# STM32F103T8.net
KiCad netlist of a schematic drawn in Altium Designer
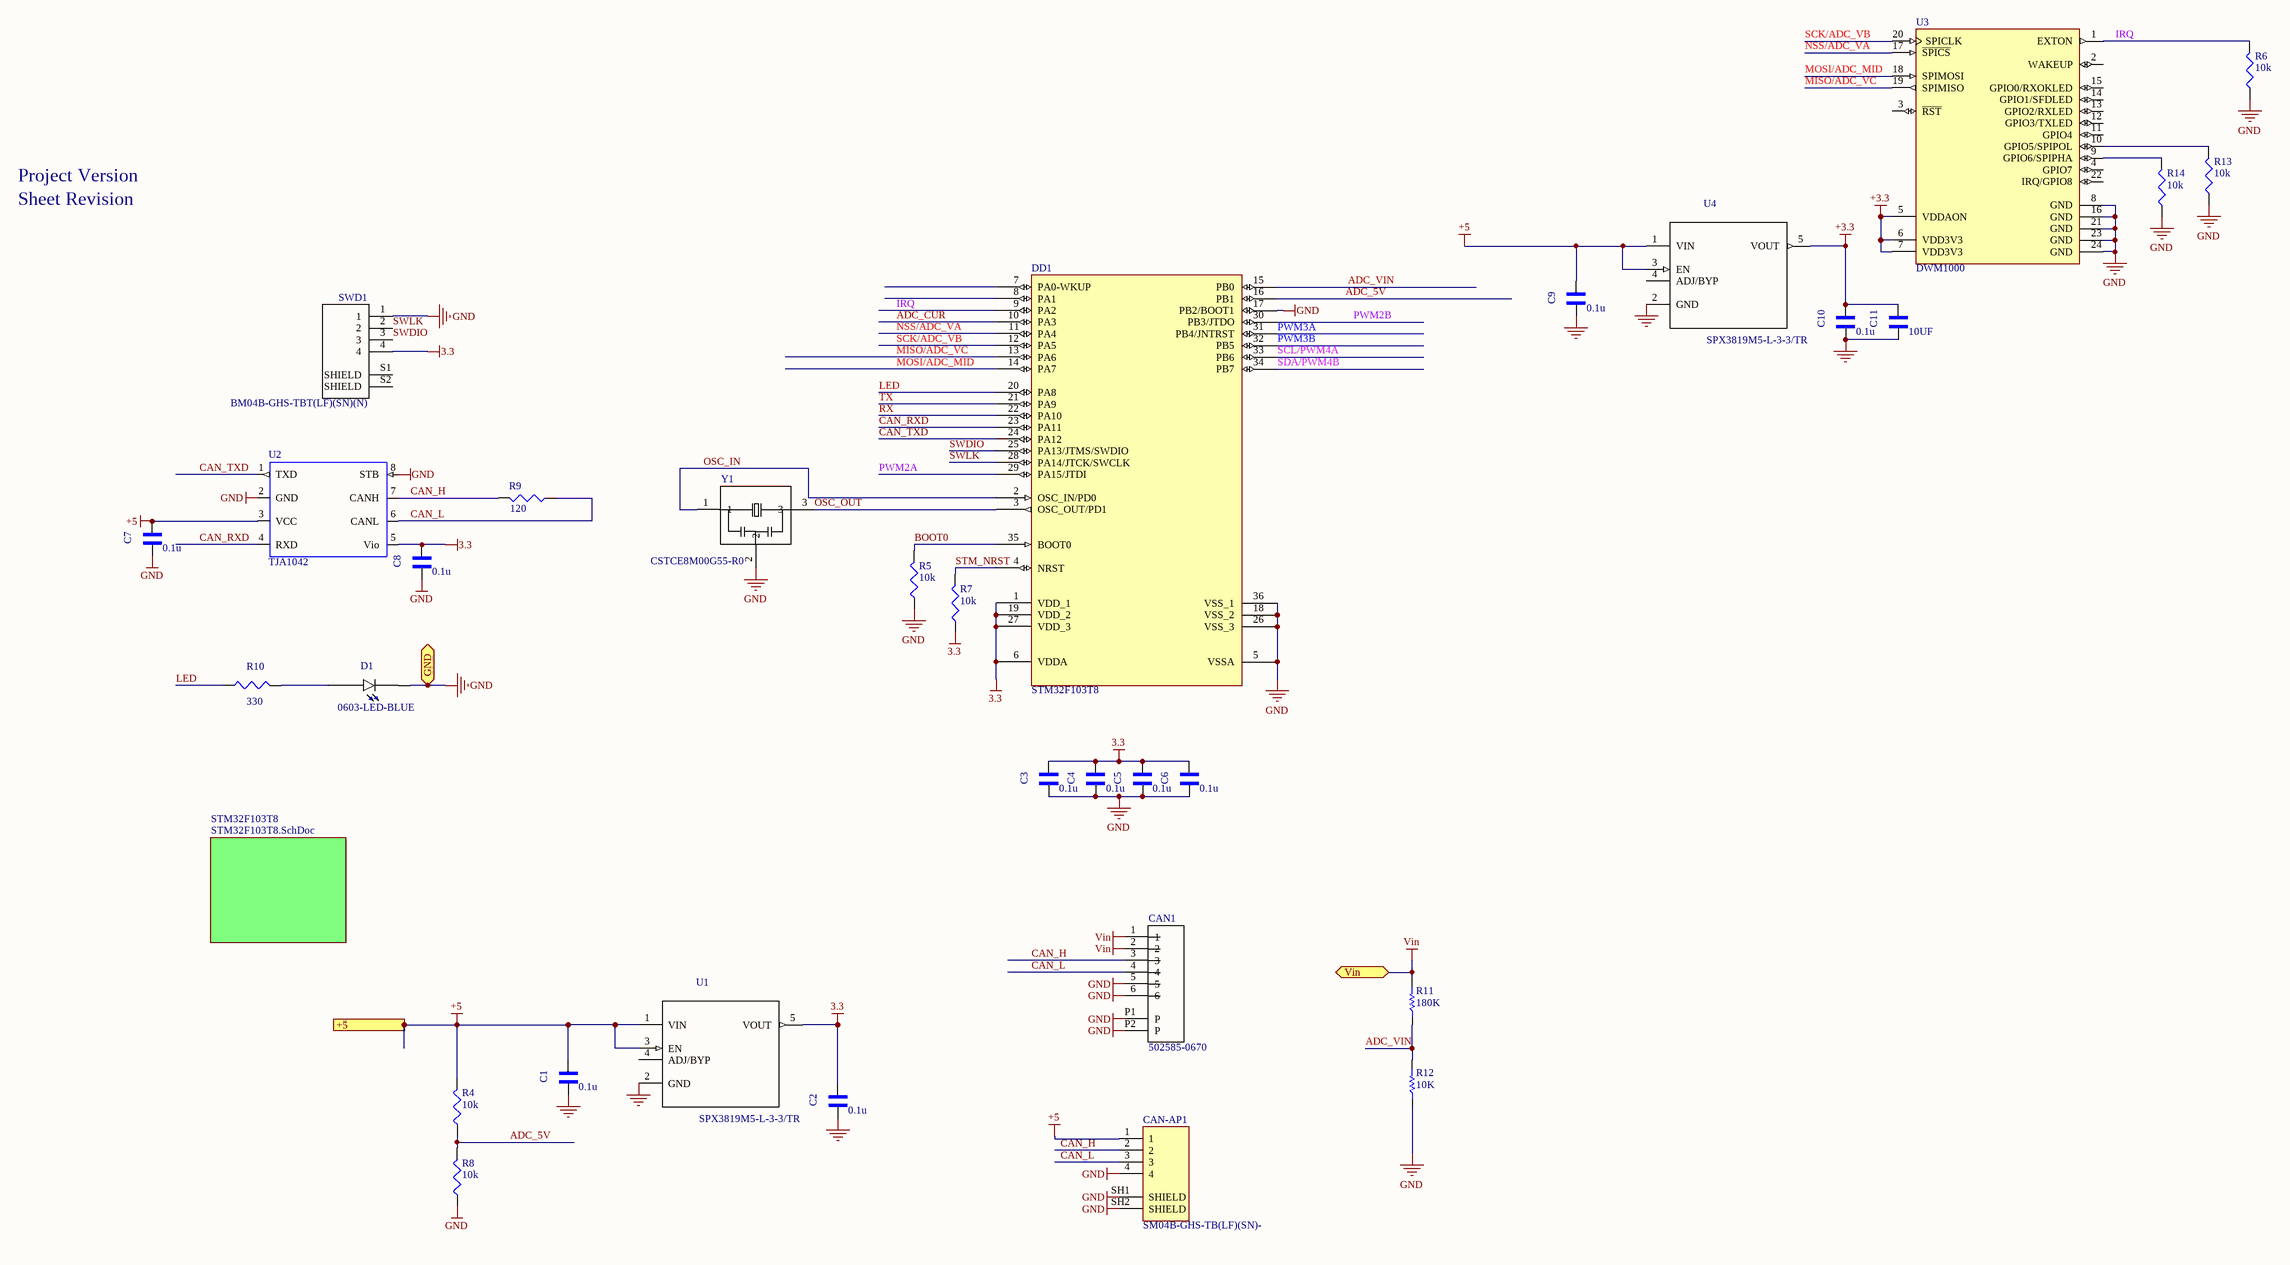
[diagram p0: STM32F103T8.SchDoc]

(export (version "E")
  (design (tool "Eeschema 10.0.6"))
  (components
    (comp (ref "C1")
      (value "0.1u")
      (footprint "*CAPC1608X90")
      (description "Cap Thin Film 0.1uf 50v 0603")
      (fields (field (name "MF") "AVX") (field (name "MP") "GX035C104MAT2-500"))
      (libsource (lib "lib") (part "GX035C104MAT2-500"))
    )
    (comp (ref "C2")
      (value "0.1u")
      (footprint "*CAPC1608X90")
      (description "Cap Thin Film 0.1uf 50v 0603")
      (fields (field (name "MF") "AVX") (field (name "MP") "GX035C104MAT2-500"))
      (libsource (lib "lib") (part "GX035C104MAT2-500"))
    )
    (comp (ref "C3")
      (value "0.1u")
      (footprint "*CAPC1608X90")
      (description "Cap Thin Film 0.1uf 50v 0603")
      (fields (field (name "MF") "AVX") (field (name "MP") "GX035C104MAT2-500 or CL10B104JB8NNNC"))
      (libsource (lib "lib") (part "GX035C104MAT2-500"))
    )
    (comp (ref "C4")
      (value "0.1u")
      (footprint "*CAPC1608X90")
      (description "Cap Thin Film 0.1uf 50v 0603")
      (fields (field (name "MF") "AVX") (field (name "MP") "GX035C104MAT2-500 or CL10B104JB8NNNC"))
      (libsource (lib "lib") (part "GX035C104MAT2-500"))
    )
    (comp (ref "C5")
      (value "0.1u")
      (footprint "*CAPC1608X90")
      (description "Cap Thin Film 0.1uf 50v 0603")
      (fields (field (name "MF") "AVX") (field (name "MP") "GX035C104MAT2-500 or CL10B104JB8NNNC"))
      (libsource (lib "lib") (part "GX035C104MAT2-500"))
    )
    (comp (ref "C6")
      (value "0.1u")
      (footprint "*CAPC1608X90")
      (description "Cap Thin Film 0.1uf 50v 0603")
      (fields (field (name "MF") "AVX") (field (name "MP") "GX035C104MAT2-500 or CL10B104JB8NNNC"))
      (libsource (lib "lib") (part "GX035C104MAT2-500"))
    )
    (comp (ref "C7")
      (value "0.1u")
      (footprint "*CAPC1608X90")
      (description "Cap Thin Film 0.1uf 50v 0603")
      (fields (field (name "MF") "AVX") (field (name "MP") "GX035C104MAT2-500 or CL10B104JB8NNNC"))
      (libsource (lib "lib") (part "GX035C104MAT2-500"))
    )
    (comp (ref "C8")
      (value "0.1u")
      (footprint "*CAPC1608X90")
      (description "Cap Thin Film 0.1uf 50v 0603")
      (fields (field (name "MF") "AVX") (field (name "MP") "GX035C104MAT2-500 or CL10B104JB8NNNC"))
      (libsource (lib "lib") (part "GX035C104MAT2-500"))
    )
    (comp (ref "C9")
      (value "0.1u")
      (footprint "*CAPC1608X90")
      (description "Cap Thin Film 0.1uf 50v 0603")
      (fields (field (name "MF") "AVX") (field (name "MP") "GX035C104MAT2-500"))
      (libsource (lib "lib") (part "GX035C104MAT2-500"))
    )
    (comp (ref "C10")
      (value "0.1u")
      (footprint "*CAPC1608X90")
      (description "Cap Thin Film 0.1uf 50v 0603")
      (fields (field (name "MF") "AVX") (field (name "MP") "GX035C104MAT2-500"))
      (libsource (lib "lib") (part "GX035C104MAT2-500"))
    )
    (comp (ref "C11")
      (value "10UF")
      (footprint "*CAPC1608X90")
      (description "Cap Thin Film 0.1uf 50v 0603")
      (fields (field (name "MF") "AVX") (field (name "MP") "GX035C104MAT2-500"))
      (libsource (lib "lib") (part "GX035C104MAT2-500"))
    )
    (comp (ref "CAN-AP1")
      (value "SM04B-GHS-TB(LF)(SN)-")
      (footprint "JST_SM04B-GHS-TB(LF)(SN)-")
      (description "Connector Header Surface Mount, Right Angle 4 position 0.049 _1.25mm_")
      (fields (field (name "MP") "SM04B-GHS-TB(LF)(SN)") (field (name "MF") "JST Sales"))
      (libsource (lib "lib") (part "SM04B-GHS-TB(LF)(SN)-"))
    )
    (comp (ref "CAN1")
      (value "502585-0670")
      (footprint "MOLEX_502585-0670")
      (fields (field (name "MF") "Molex"))
      (libsource (lib "lib") (part "502585-0670"))
    )
    (comp (ref "D1")
      (value "0603-LED-BLUE")
      (footprint "*LEDM1608X80_LTE-C1906R-14(Primary)")
      (description "LED IrLED Chip LED 2-Pin SMD T/R")
      (libsource (lib "lib") (part "LTE-C1906R-14"))
    )
    (comp (ref "DD1")
      (value "STM32F103T8")
      (footprint "*QFN50P600X600X100-37N")
      (description "STM32F103T8U6, Микроконтроллер 32BIT ARM 64K FLASH [VFQFPN-36]")
      (fields (field (name "MF") "STM") (field (name "MP") "STM32F103T8U6"))
      (libsource (lib "lib") (part "STM32F103T8"))
    )
    (comp (ref "R4")
      (value "10k")
      (footprint "J1-0603")
      (description "10 kOhms 1 0.1 W 1 10 W Chip Resistor 0603 1608 Metric Thick Film")
      (fields (field (name "MF") "Yageo or NXP") (field (name "MP") "10K 1% 0603"))
      (libsource (lib "CAN_NODE_MINI") (part "RC0603FR-0710KL"))
    )
    (comp (ref "R5")
      (value "10k")
      (footprint "J1-0603")
      (description "10 kOhms 1 0.1 W 1 10 W Chip Resistor 0603 1608 Metric Thick Film")
      (fields (field (name "MF") "Yageo or NXP") (field (name "MP") "10K 1% 0603"))
      (libsource (lib "CAN_NODE_MINI") (part "RC0603FR-0710KL"))
    )
    (comp (ref "R6")
      (value "10k")
      (footprint "J1-0603")
      (description "10 kOhms 1 0.1 W 1 10 W Chip Resistor 0603 1608 Metric Thick Film")
      (fields (field (name "MF") "Yageo or NXP") (field (name "MP") "10K 1% 0603"))
      (libsource (lib "CAN_NODE_MINI") (part "RC0603FR-0710KL"))
    )
    (comp (ref "R7")
      (value "10k")
      (footprint "J1-0603")
      (description "10 kOhms 1 0.1 W 1 10 W Chip Resistor 0603 1608 Metric Thick Film")
      (fields (field (name "MF") "Yageo or NXP") (field (name "MP") "10K 1% 0603"))
      (libsource (lib "CAN_NODE_MINI") (part "RC0603FR-0710KL"))
    )
    (comp (ref "R8")
      (value "10k")
      (footprint "J1-0603")
      (description "10 kOhms 1 0.1 W 1 10 W Chip Resistor 0603 1608 Metric Thick Film")
      (fields (field (name "MF") "Yageo or NXP") (field (name "MP") "10K 1% 0603"))
      (libsource (lib "CAN_NODE_MINI") (part "RC0603FR-0710KL"))
    )
    (comp (ref "R9")
      (value "120")
      (footprint "J1-0603")
      (description "120 Ohms 1 0.1 W 1 10 W Chip Resistor 0603 1608 Metric Thick Film")
      (fields (field (name "MP") "RC0603FR-07120RL") (field (name "Comment") "Res3"))
      (libsource (lib "Miscellaneous Devices") (part "Res3"))
    )
    (comp (ref "R10")
      (value "330")
      (footprint "J1-0603")
      (description "Resistor")
      (fields (field (name "MP") "RC0603FR-07330RL") (field (name "Comment") "Res3"))
      (libsource (lib "Miscellaneous Devices") (part "Res3"))
    )
    (comp (ref "R11")
      (value "180K")
      (footprint "RES 0603 (1608X06L)")
      (description "Resistor")
      (fields (field (name "TOLERANCE") "5%") (field (name "POWER") "1/8 W"))
      (libsource (lib "R2T Team Library") (part "Resistor"))
    )
    (comp (ref "R12")
      (value "10K")
      (footprint "RES 0603 (1608X06L)")
      (description "Resistor")
      (fields (field (name "TOLERANCE") "5%") (field (name "POWER") "1/8 W"))
      (libsource (lib "R2T Team Library") (part "Resistor"))
    )
    (comp (ref "R13")
      (value "10k")
      (footprint "J1-0603")
      (description "10 kOhms 1 0.1 W 1 10 W Chip Resistor 0603 1608 Metric Thick Film")
      (fields (field (name "MF") "Yageo or NXP") (field (name "MP") "10K 1% 0603"))
      (libsource (lib "CAN_NODE_MINI") (part "RC0603FR-0710KL"))
    )
    (comp (ref "R14")
      (value "10k")
      (footprint "J1-0603")
      (description "10 kOhms 1 0.1 W 1 10 W Chip Resistor 0603 1608 Metric Thick Film")
      (fields (field (name "MF") "Yageo or NXP") (field (name "MP") "10K 1% 0603"))
      (libsource (lib "CAN_NODE_MINI") (part "RC0603FR-0710KL"))
    )
    (comp (ref "SWD1")
      (value "BM04B-GHS-TBT(LF)(SN)(N)")
      (footprint "JST_BM04B-GHS-holes")
      (description "Conn Shrouded Header HDR 4 POS 1.25mm Solder ST SMD Reel")
      (fields (field (name "MF") "JST Sales") (field (name "MP") "SM04B-GHS-TB(LF)(SN)"))
      (libsource (lib "lib") (part "BM04B-GHS-TBT(LF)(SN)(N)"))
    )
    (comp (ref "U1")
      (value "SPX3819M5-L-3-3/TR")
      (footprint "*SOT95P280X145-5N")
      (description "Low Dropout Voltage Regulator, Adjustable 0.5A, В±1%, 2.5 to 16 Vin, 5-Pin SOT-23")
      (fields (field (name "MF") "MaxLinear, Inc."))
      (libsource (lib "DC_DC") (part "SPX3819M5-L"))
    )
    (comp (ref "U2")
      (value "TJA1042")
      (footprint "SOT782-1")
      (description "1/1 Transceiver Half CANbus 8-SO")
      (fields (field (name "MF") "NXP USA"))
      (libsource (lib "lib") (part "TJA1042"))
    )
    (comp (ref "U3")
      (value "DWM1000")
      (footprint "DECW-DWM1000-24_V")
      (description "DW M1000 IEEE 802.15.4 -2011 UWB Transceiver Module")
      (fields (field (name "MANUFACTURER") "Decawave"))
      (libsource (lib "Altium Content Vault") (part "DECW-DWM1000-24"))
    )
    (comp (ref "U4")
      (value "SPX3819M5-L-3-3/TR")
      (footprint "*SOT95P280X145-5N")
      (description "Low Dropout Voltage Regulator, Adjustable 0.5A, В±1%, 2.5 to 16 Vin, 5-Pin SOT-23")
      (fields (field (name "MF") "MaxLinear, Inc."))
      (libsource (lib "DC_DC") (part "SPX3819M5-L"))
    )
    (comp (ref "Y1")
      (value "CSTCE8M00G55-R0")
      (footprint "*OSC_CSTCE8M00G55-R0")
      (description "Ceramic Resonator 8MHz ??0.5% _Tol_ ??0.2% _Stability_ 33pF 40Ohm 3-Pin CSMD T/R")
      (fields (field (name "MF") "Murata"))
      (libsource (lib "DC_DC") (part "CSTCE8M00G55-R0"))
    )
  )
  (nets
    (net (code "1") (name "+3.3") (class "Default")
      (node (ref "C10") (pin "1") (pinfunction "1_1") (pintype "passive"))
      (node (ref "C11") (pin "1") (pinfunction "1_1") (pintype "passive"))
      (node (ref "U3") (pin "5") (pinfunction "VDDAON_5") (pintype "power_in"))
      (node (ref "U3") (pin "6") (pinfunction "VDD3V3_6") (pintype "power_in"))
      (node (ref "U3") (pin "7") (pinfunction "VDD3V3_7") (pintype "power_in"))
      (node (ref "U4") (pin "5") (pinfunction "VOUT_5") (pintype "output"))
    )
    (net (code "2") (name "+5") (class "Default")
      (node (ref "C1") (pin "1") (pinfunction "1_1") (pintype "passive"))
      (node (ref "C7") (pin "1") (pinfunction "1_1") (pintype "passive"))
      (node (ref "C9") (pin "1") (pinfunction "1_1") (pintype "passive"))
      (node (ref "CAN-AP1") (pin "1") (pinfunction "1_1") (pintype "passive"))
      (node (ref "R4") (pin "2") (pinfunction "2_2") (pintype "passive"))
      (node (ref "U1") (pin "1") (pinfunction "VIN_1") (pintype "power_in"))
      (node (ref "U1") (pin "3") (pinfunction "EN_3") (pintype "input"))
      (node (ref "U2") (pin "3") (pinfunction "VCC_3") (pintype "power_in"))
      (node (ref "U4") (pin "1") (pinfunction "VIN_1") (pintype "power_in"))
      (node (ref "U4") (pin "3") (pinfunction "EN_3") (pintype "input"))
    )
    (net (code "3") (name "/ADC_5V") (class "Default")
      (node (ref "DD1") (pin "16") (pinfunction "PB1_16") (pintype "bidirectional"))
      (node (ref "R4") (pin "1") (pinfunction "1_1") (pintype "passive"))
      (node (ref "R8") (pin "2") (pinfunction "2_2") (pintype "passive"))
    )
    (net (code "4") (name "/ADC_CUR") (class "Default")
      (node (ref "DD1") (pin "10") (pinfunction "PA3_10") (pintype "bidirectional"))
    )
    (net (code "5") (name "/ADC_VIN") (class "Default")
      (node (ref "DD1") (pin "15") (pinfunction "PB0_15") (pintype "bidirectional"))
      (node (ref "R11") (pin "1") (pinfunction "1_1") (pintype "passive"))
      (node (ref "R12") (pin "2") (pinfunction "2_2") (pintype "passive"))
    )
    (net (code "6") (name "/BOOT0") (class "Default")
      (node (ref "DD1") (pin "35") (pinfunction "BOOT0_35") (pintype "input"))
      (node (ref "R5") (pin "2") (pinfunction "2_2") (pintype "passive"))
    )
    (net (code "7") (name "/CAN_H") (class "Default")
      (node (ref "CAN-AP1") (pin "2") (pinfunction "2_2") (pintype "passive"))
      (node (ref "CAN1") (pin "3") (pinfunction "3_3") (pintype "passive"))
      (node (ref "R9") (pin "2") (pinfunction "2_2") (pintype "passive"))
      (node (ref "U2") (pin "7") (pinfunction "CANH_7") (pintype "bidirectional"))
    )
    (net (code "8") (name "/CAN_L") (class "Default")
      (node (ref "CAN-AP1") (pin "3") (pinfunction "3_3") (pintype "passive"))
      (node (ref "CAN1") (pin "4") (pinfunction "4_4") (pintype "passive"))
      (node (ref "R9") (pin "1") (pinfunction "1_1") (pintype "passive"))
      (node (ref "U2") (pin "6") (pinfunction "CANL_6") (pintype "bidirectional"))
    )
    (net (code "9") (name "/CAN_RXD") (class "Default")
      (node (ref "DD1") (pin "23") (pinfunction "PA11_23") (pintype "bidirectional"))
      (node (ref "U2") (pin "4") (pinfunction "RXD_4") (pintype "bidirectional"))
    )
    (net (code "10") (name "/CAN_TXD") (class "Default")
      (node (ref "DD1") (pin "24") (pinfunction "PA12_24") (pintype "bidirectional"))
      (node (ref "U2") (pin "1") (pinfunction "TXD_1") (pintype "output"))
    )
    (net (code "11") (name "/IRQ") (class "Default")
      (node (ref "DD1") (pin "9") (pinfunction "PA2_9") (pintype "bidirectional"))
      (node (ref "R6") (pin "2") (pinfunction "2_2") (pintype "passive"))
      (node (ref "U3") (pin "1") (pinfunction "EXTON_1") (pintype "output"))
    )
    (net (code "12") (name "/LED") (class "Default")
      (node (ref "DD1") (pin "20") (pinfunction "PA8_20") (pintype "bidirectional"))
      (node (ref "R10") (pin "1") (pinfunction "1_1") (pintype "passive"))
    )
    (net (code "13") (name "/MISO{slash}ADC_VC") (class "Default")
      (node (ref "DD1") (pin "13") (pinfunction "PA6_13") (pintype "bidirectional"))
      (node (ref "U3") (pin "19") (pinfunction "SPIMISO_19") (pintype "output"))
    )
    (net (code "14") (name "/MOSI{slash}ADC_MID") (class "Default")
      (node (ref "DD1") (pin "14") (pinfunction "PA7_14") (pintype "bidirectional"))
      (node (ref "U3") (pin "18") (pinfunction "SPIMOSI_18") (pintype "input"))
    )
    (net (code "15") (name "/NSS{slash}ADC_VA") (class "Default")
      (node (ref "DD1") (pin "11") (pinfunction "PA4_11") (pintype "bidirectional"))
      (node (ref "U3") (pin "17") (pinfunction "~{SPICS}_17") (pintype "input"))
    )
    (net (code "16") (name "/OSC_IN") (class "Default")
      (node (ref "DD1") (pin "2") (pinfunction "OSC_IN/PD0_2") (pintype "input"))
      (node (ref "Y1") (pin "1") (pinfunction "1_1") (pintype "passive"))
    )
    (net (code "17") (name "/OSC_OUT") (class "Default")
      (node (ref "DD1") (pin "3") (pinfunction "OSC_OUT/PD1_3") (pintype "output"))
      (node (ref "Y1") (pin "3") (pinfunction "3_3") (pintype "passive"))
    )
    (net (code "18") (name "/PWM2A") (class "Default")
      (node (ref "DD1") (pin "29") (pinfunction "PA15/JTDI_29") (pintype "bidirectional"))
    )
    (net (code "19") (name "/PWM2B") (class "Default")
      (node (ref "DD1") (pin "30") (pinfunction "PB3/JTDO_30") (pintype "bidirectional"))
    )
    (net (code "20") (name "/PWM3A") (class "Default")
      (node (ref "DD1") (pin "31") (pinfunction "PB4/JNTRST_31") (pintype "bidirectional"))
    )
    (net (code "21") (name "/PWM3B") (class "Default")
      (node (ref "DD1") (pin "32") (pinfunction "PB5_32") (pintype "bidirectional"))
    )
    (net (code "22") (name "/RX") (class "Default")
      (node (ref "DD1") (pin "22") (pinfunction "PA10_22") (pintype "bidirectional"))
    )
    (net (code "23") (name "/SCK{slash}ADC_VB") (class "Default")
      (node (ref "DD1") (pin "12") (pinfunction "PA5_12") (pintype "bidirectional"))
      (node (ref "U3") (pin "20") (pinfunction "SPICLK_20") (pintype "input"))
    )
    (net (code "24") (name "/SCL{slash}PWM4A") (class "Default")
      (node (ref "DD1") (pin "33") (pinfunction "PB6_33") (pintype "bidirectional"))
    )
    (net (code "25") (name "/SDA{slash}PWM4B") (class "Default")
      (node (ref "DD1") (pin "34") (pinfunction "PB7_34") (pintype "bidirectional"))
    )
    (net (code "26") (name "/STM_NRST") (class "Default")
      (node (ref "DD1") (pin "4") (pinfunction "NRST_4") (pintype "bidirectional"))
      (node (ref "R7") (pin "2") (pinfunction "2_2") (pintype "passive"))
    )
    (net (code "27") (name "/SWDIO") (class "Default")
      (node (ref "DD1") (pin "25") (pinfunction "PA13/JTMS/SWDIO_25") (pintype "bidirectional"))
      (node (ref "SWD1") (pin "3") (pinfunction "3_3") (pintype "passive"))
    )
    (net (code "28") (name "/SWLK") (class "Default")
      (node (ref "DD1") (pin "28") (pinfunction "PA14/JTCK/SWCLK_28") (pintype "bidirectional"))
      (node (ref "SWD1") (pin "2") (pinfunction "2_2") (pintype "passive"))
    )
    (net (code "29") (name "/TX") (class "Default")
      (node (ref "DD1") (pin "21") (pinfunction "PA9_21") (pintype "bidirectional"))
    )
    (net (code "30") (name "3.3") (class "Default")
      (node (ref "C2") (pin "1") (pinfunction "1_1") (pintype "passive"))
      (node (ref "C3") (pin "1") (pinfunction "1_1") (pintype "passive"))
      (node (ref "C4") (pin "1") (pinfunction "1_1") (pintype "passive"))
      (node (ref "C5") (pin "1") (pinfunction "1_1") (pintype "passive"))
      (node (ref "C6") (pin "1") (pinfunction "1_1") (pintype "passive"))
      (node (ref "C8") (pin "1") (pinfunction "1_1") (pintype "passive"))
      (node (ref "DD1") (pin "1") (pinfunction "VDD_1_1") (pintype "power_in"))
      (node (ref "DD1") (pin "19") (pinfunction "VDD_2_19") (pintype "power_in"))
      (node (ref "DD1") (pin "27") (pinfunction "VDD_3_27") (pintype "power_in"))
      (node (ref "DD1") (pin "6") (pinfunction "VDDA_6") (pintype "power_in"))
      (node (ref "R7") (pin "1") (pinfunction "1_1") (pintype "passive"))
      (node (ref "SWD1") (pin "4") (pinfunction "4_4") (pintype "passive"))
      (node (ref "U1") (pin "5") (pinfunction "VOUT_5") (pintype "output"))
      (node (ref "U2") (pin "5") (pinfunction "Vio_5") (pintype "power_in"))
    )
    (net (code "31") (name "GND") (class "Default")
      (node (ref "C1") (pin "2") (pinfunction "2_2") (pintype "passive"))
      (node (ref "C10") (pin "2") (pinfunction "2_2") (pintype "passive"))
      (node (ref "C11") (pin "2") (pinfunction "2_2") (pintype "passive"))
      (node (ref "C2") (pin "2") (pinfunction "2_2") (pintype "passive"))
      (node (ref "C3") (pin "2") (pinfunction "2_2") (pintype "passive"))
      (node (ref "C4") (pin "2") (pinfunction "2_2") (pintype "passive"))
      (node (ref "C5") (pin "2") (pinfunction "2_2") (pintype "passive"))
      (node (ref "C6") (pin "2") (pinfunction "2_2") (pintype "passive"))
      (node (ref "C7") (pin "2") (pinfunction "2_2") (pintype "passive"))
      (node (ref "C8") (pin "2") (pinfunction "2_2") (pintype "passive"))
      (node (ref "C9") (pin "2") (pinfunction "2_2") (pintype "passive"))
      (node (ref "CAN-AP1") (pin "4") (pinfunction "4_4") (pintype "passive"))
      (node (ref "CAN-AP1") (pin "SH1") (pinfunction "SHIELD_SH1") (pintype "power_in"))
      (node (ref "CAN-AP1") (pin "SH2") (pinfunction "SHIELD_SH2") (pintype "power_in"))
      (node (ref "CAN1") (pin "5") (pinfunction "5_5") (pintype "passive"))
      (node (ref "CAN1") (pin "6") (pinfunction "6_6") (pintype "passive"))
      (node (ref "CAN1") (pin "P1") (pinfunction "P_P1") (pintype "passive"))
      (node (ref "CAN1") (pin "P2") (pinfunction "P_P2") (pintype "passive"))
      (node (ref "D1") (pin "C") (pinfunction "C_C") (pintype "passive"))
      (node (ref "DD1") (pin "17") (pinfunction "PB2/BOOT1_17") (pintype "bidirectional"))
      (node (ref "DD1") (pin "18") (pinfunction "VSS_2_18") (pintype "power_in"))
      (node (ref "DD1") (pin "26") (pinfunction "VSS_3_26") (pintype "power_in"))
      (node (ref "DD1") (pin "36") (pinfunction "VSS_1_36") (pintype "power_in"))
      (node (ref "DD1") (pin "5") (pinfunction "VSSA_5") (pintype "power_in"))
      (node (ref "R12") (pin "1") (pinfunction "1_1") (pintype "passive"))
      (node (ref "R13") (pin "1") (pinfunction "1_1") (pintype "passive"))
      (node (ref "R14") (pin "1") (pinfunction "1_1") (pintype "passive"))
      (node (ref "R5") (pin "1") (pinfunction "1_1") (pintype "passive"))
      (node (ref "R6") (pin "1") (pinfunction "1_1") (pintype "passive"))
      (node (ref "R8") (pin "1") (pinfunction "1_1") (pintype "passive"))
      (node (ref "SWD1") (pin "1") (pinfunction "1_1") (pintype "passive"))
      (node (ref "U1") (pin "2") (pinfunction "GND_2") (pintype "passive"))
      (node (ref "U2") (pin "2") (pinfunction "GND_2") (pintype "power_in"))
      (node (ref "U2") (pin "8") (pinfunction "STB_8") (pintype "input"))
      (node (ref "U3") (pin "16") (pinfunction "GND_16") (pintype "power_in"))
      (node (ref "U3") (pin "21") (pinfunction "GND_21") (pintype "power_in"))
      (node (ref "U3") (pin "23") (pinfunction "GND_23") (pintype "power_in"))
      (node (ref "U3") (pin "24") (pinfunction "GND_24") (pintype "power_in"))
      (node (ref "U3") (pin "8") (pinfunction "GND_8") (pintype "power_in"))
      (node (ref "U4") (pin "2") (pinfunction "GND_2") (pintype "passive"))
      (node (ref "Y1") (pin "2") (pinfunction "2_2") (pintype "power_in"))
    )
    (net (code "32") (name "Net-(D1-PadA)") (class "Default")
      (node (ref "D1") (pin "A") (pinfunction "A_A") (pintype "passive"))
      (node (ref "R10") (pin "2") (pinfunction "2_2") (pintype "passive"))
    )
    (net (code "33") (name "Net-(U3-GPIO5{slash}SPIPOL)") (class "Default")
      (node (ref "R13") (pin "2") (pinfunction "2_2") (pintype "passive"))
      (node (ref "U3") (pin "10") (pinfunction "GPIO5/SPIPOL_10") (pintype "bidirectional"))
    )
    (net (code "34") (name "Net-(U3-GPIO6{slash}SPIPHA)") (class "Default")
      (node (ref "R14") (pin "2") (pinfunction "2_2") (pintype "passive"))
      (node (ref "U3") (pin "9") (pinfunction "GPIO6/SPIPHA_9") (pintype "bidirectional"))
    )
    (net (code "35") (name "Vin") (class "Default")
      (node (ref "CAN1") (pin "1") (pinfunction "1_1") (pintype "passive"))
      (node (ref "CAN1") (pin "2") (pinfunction "2_2") (pintype "passive"))
      (node (ref "R11") (pin "2") (pinfunction "2_2") (pintype "passive"))
    )
    (net (code "36") (name "unconnected-(DD1-PA0-WKUP-Pad7)") (class "Default")
      (node (ref "DD1") (pin "7") (pinfunction "PA0-WKUP_7") (pintype "bidirectional"))
    )
    (net (code "37") (name "unconnected-(DD1-PA1-Pad8)") (class "Default")
      (node (ref "DD1") (pin "8") (pinfunction "PA1_8") (pintype "bidirectional"))
    )
    (net (code "38") (name "unconnected-(SWD1-SHIELD-PadS1)") (class "Default")
      (node (ref "SWD1") (pin "S1") (pinfunction "SHIELD_S1") (pintype "passive"))
    )
    (net (code "39") (name "unconnected-(SWD1-SHIELD-PadS2)") (class "Default")
      (node (ref "SWD1") (pin "S2") (pinfunction "SHIELD_S2") (pintype "passive"))
    )
    (net (code "40") (name "unconnected-(U1-ADJ{slash}BYP-Pad4)") (class "Default")
      (node (ref "U1") (pin "4") (pinfunction "ADJ/BYP_4") (pintype "passive"))
    )
    (net (code "41") (name "unconnected-(U3-GPIO0{slash}RXOKLED-Pad15)") (class "Default")
      (node (ref "U3") (pin "15") (pinfunction "GPIO0/RXOKLED_15") (pintype "bidirectional"))
    )
    (net (code "42") (name "unconnected-(U3-GPIO1{slash}SFDLED-Pad14)") (class "Default")
      (node (ref "U3") (pin "14") (pinfunction "GPIO1/SFDLED_14") (pintype "bidirectional"))
    )
    (net (code "43") (name "unconnected-(U3-GPIO2{slash}RXLED-Pad13)") (class "Default")
      (node (ref "U3") (pin "13") (pinfunction "GPIO2/RXLED_13") (pintype "bidirectional"))
    )
    (net (code "44") (name "unconnected-(U3-GPIO3{slash}TXLED-Pad12)") (class "Default")
      (node (ref "U3") (pin "12") (pinfunction "GPIO3/TXLED_12") (pintype "bidirectional"))
    )
    (net (code "45") (name "unconnected-(U3-GPIO4-Pad11)") (class "Default")
      (node (ref "U3") (pin "11") (pinfunction "GPIO4_11") (pintype "bidirectional"))
    )
    (net (code "46") (name "unconnected-(U3-GPIO7-Pad4)") (class "Default")
      (node (ref "U3") (pin "4") (pinfunction "GPIO7_4") (pintype "bidirectional"))
    )
    (net (code "47") (name "unconnected-(U3-IRQ{slash}GPIO8-Pad22)") (class "Default")
      (node (ref "U3") (pin "22") (pinfunction "IRQ/GPIO8_22") (pintype "bidirectional"))
    )
    (net (code "48") (name "unconnected-(U3-WAKEUP-Pad2)") (class "Default")
      (node (ref "U3") (pin "2") (pinfunction "WAKEUP_2") (pintype "bidirectional"))
    )
    (net (code "49") (name "unconnected-(U3-~{RST}-Pad3)") (class "Default")
      (node (ref "U3") (pin "3") (pinfunction "~{RST}_3") (pintype "bidirectional"))
    )
    (net (code "50") (name "unconnected-(U4-ADJ{slash}BYP-Pad4)") (class "Default")
      (node (ref "U4") (pin "4") (pinfunction "ADJ/BYP_4") (pintype "passive"))
    )
  )
)
